# Serial.net
KiCad netlist of a schematic drawn in Altium Designer
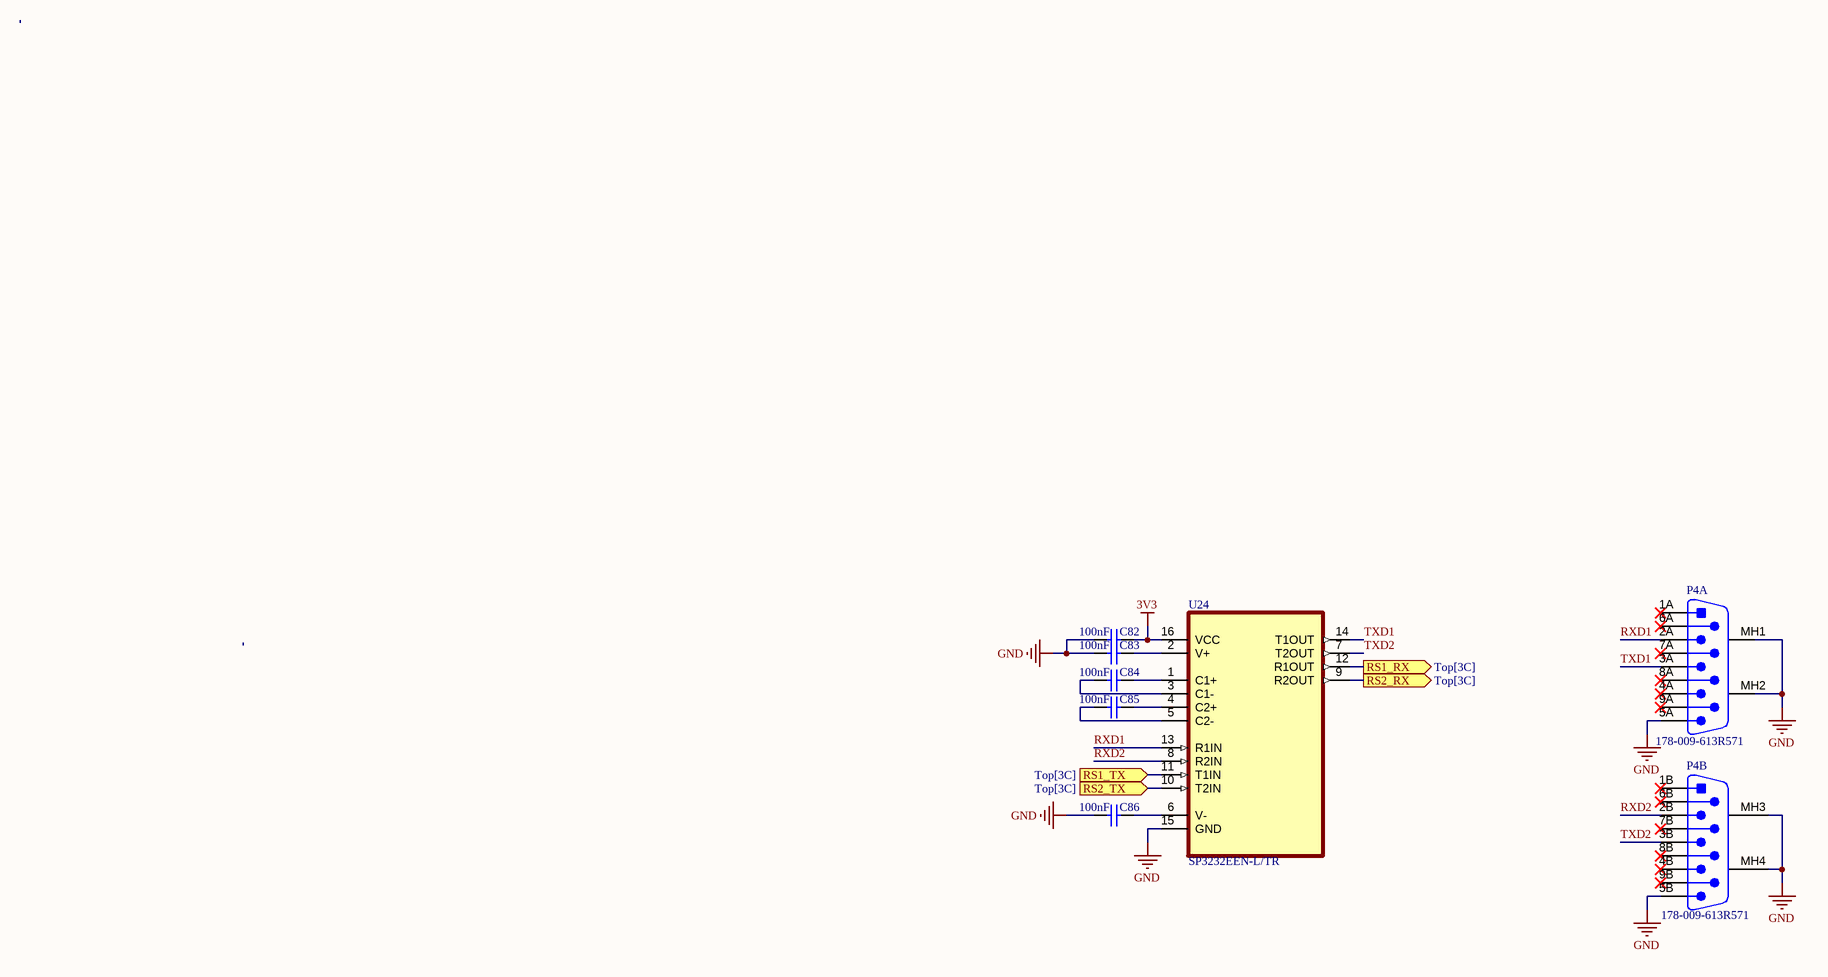
[diagram p0: Serial.SchDoc]

(export (version "E")
  (design (tool "Eeschema 10.0.6"))
  (components
    (comp (ref "C82")
      (value "100nF")
      (description "Capacitor")
      (libsource (lib "Simulation Generic Components") (part "Capacitor"))
    )
    (comp (ref "C83")
      (value "100nF")
      (description "Capacitor")
      (libsource (lib "Simulation Generic Components") (part "Capacitor"))
    )
    (comp (ref "C84")
      (value "100nF")
      (description "Capacitor")
      (libsource (lib "Simulation Generic Components") (part "Capacitor"))
    )
    (comp (ref "C85")
      (value "100nF")
      (description "Capacitor")
      (libsource (lib "Simulation Generic Components") (part "Capacitor"))
    )
    (comp (ref "C86")
      (value "100nF")
      (description "Capacitor")
      (libsource (lib "Simulation Generic Components") (part "Capacitor"))
    )
    (comp (ref "P4")
      (value "178-009-613R571")
      (footprint "NORCO-178-009-613R571_V")
      (description "D-Sub Connector, Stacked Plug, RA, -55 to 105 degC, 18-Pin THD, RoHS, Tray")
      (fields (field (name "MANUFACTURER") "Norcomp"))
      (libsource (lib "Altium Content Vault") (part "CN-2S-4M-D18_A"))
    )
    (comp (ref "U24")
      (value "SP3232EEN-L/TR")
      (footprint "SOIC127P600X175-16N")
      (description "2/2 Transceiver Full RS232 16-SOIC")
      (fields (field (name "MF") "MaxLinear, Inc."))
      (libsource (lib "GSSM Golf Cart") (part "SP3232EEN-L/TR"))
    )
  )
  (nets
    (net (code "1") (name "/RS1_RX") (class "Default")
      (node (ref "U24") (pin "12") (pinfunction "R1OUT_12") (pintype "output"))
    )
    (net (code "2") (name "/RS1_TX") (class "Default")
      (node (ref "U24") (pin "11") (pinfunction "T1IN_11") (pintype "input"))
    )
    (net (code "3") (name "/RS2_RX") (class "Default")
      (node (ref "U24") (pin "9") (pinfunction "R2OUT_9") (pintype "output"))
    )
    (net (code "4") (name "/RS2_TX") (class "Default")
      (node (ref "U24") (pin "10") (pinfunction "T2IN_10") (pintype "input"))
    )
    (net (code "5") (name "/RXD1") (class "Default")
      (node (ref "P4") (pin "2A") (pinfunction "2A_2A") (pintype "passive"))
      (node (ref "U24") (pin "13") (pinfunction "R1IN_13") (pintype "input"))
    )
    (net (code "6") (name "/RXD2") (class "Default")
      (node (ref "P4") (pin "2B") (pinfunction "2B_2B") (pintype "passive"))
      (node (ref "U24") (pin "8") (pinfunction "R2IN_8") (pintype "input"))
    )
    (net (code "7") (name "/TXD1") (class "Default")
      (node (ref "P4") (pin "3A") (pinfunction "6A_3A") (pintype "passive"))
      (node (ref "U24") (pin "14") (pinfunction "T1OUT_14") (pintype "output"))
    )
    (net (code "8") (name "/TXD2") (class "Default")
      (node (ref "P4") (pin "3B") (pinfunction "3B_3B") (pintype "passive"))
      (node (ref "U24") (pin "7") (pinfunction "T2OUT_7") (pintype "output"))
    )
    (net (code "9") (name "3V3") (class "Default")
      (node (ref "C82") (pin "1") (pinfunction "1_1") (pintype "passive"))
      (node (ref "U24") (pin "16") (pinfunction "VCC_16") (pintype "power_in"))
    )
    (net (code "10") (name "GND") (class "Default")
      (node (ref "C82") (pin "2") (pinfunction "2_2") (pintype "passive"))
      (node (ref "C83") (pin "2") (pinfunction "2_2") (pintype "passive"))
      (node (ref "C86") (pin "2") (pinfunction "2_2") (pintype "passive"))
      (node (ref "P4") (pin "5A") (pinfunction "4A_5A") (pintype "passive"))
      (node (ref "P4") (pin "5B") (pinfunction "5B_5B") (pintype "passive"))
      (node (ref "P4") (pin "MH1") (pinfunction "MH1_MH1") (pintype "passive"))
      (node (ref "P4") (pin "MH2") (pinfunction "MH2_MH2") (pintype "passive"))
      (node (ref "P4") (pin "MH3") (pinfunction "MH3_MH3") (pintype "passive"))
      (node (ref "P4") (pin "MH4") (pinfunction "MH4_MH4") (pintype "passive"))
      (node (ref "U24") (pin "15") (pinfunction "GND_15") (pintype "passive"))
    )
    (net (code "11") (name "Net-(U24-C1+)") (class "Default")
      (node (ref "C84") (pin "1") (pinfunction "1_1") (pintype "passive"))
      (node (ref "U24") (pin "1") (pinfunction "C1+_1") (pintype "passive"))
    )
    (net (code "12") (name "Net-(U24-C1-)") (class "Default")
      (node (ref "C84") (pin "2") (pinfunction "2_2") (pintype "passive"))
      (node (ref "U24") (pin "3") (pinfunction "C1-_3") (pintype "passive"))
    )
    (net (code "13") (name "Net-(U24-C2+)") (class "Default")
      (node (ref "C85") (pin "1") (pinfunction "1_1") (pintype "passive"))
      (node (ref "U24") (pin "4") (pinfunction "C2+_4") (pintype "passive"))
    )
    (net (code "14") (name "Net-(U24-C2-)") (class "Default")
      (node (ref "C85") (pin "2") (pinfunction "2_2") (pintype "passive"))
      (node (ref "U24") (pin "5") (pinfunction "C2-_5") (pintype "passive"))
    )
    (net (code "15") (name "Net-(U24-V+)") (class "Default")
      (node (ref "C83") (pin "1") (pinfunction "1_1") (pintype "passive"))
      (node (ref "U24") (pin "2") (pinfunction "V+_2") (pintype "power_in"))
    )
    (net (code "16") (name "Net-(U24-V-)") (class "Default")
      (node (ref "C86") (pin "1") (pinfunction "1_1") (pintype "passive"))
      (node (ref "U24") (pin "6") (pinfunction "V-_6") (pintype "power_in"))
    )
    (net (code "17") (name "unconnected-(P4-Pad1A)") (class "Default")
      (node (ref "P4") (pin "1A") (pinfunction "1A_1A") (pintype "passive+no_connect"))
    )
    (net (code "18") (name "unconnected-(P4-Pad1B)") (class "Default")
      (node (ref "P4") (pin "1B") (pinfunction "1B_1B") (pintype "passive+no_connect"))
    )
    (net (code "19") (name "unconnected-(P4-Pad4B)") (class "Default")
      (node (ref "P4") (pin "4B") (pinfunction "4B_4B") (pintype "passive+no_connect"))
    )
    (net (code "20") (name "unconnected-(P4-Pad6B)") (class "Default")
      (node (ref "P4") (pin "6B") (pinfunction "6B_6B") (pintype "passive+no_connect"))
    )
    (net (code "21") (name "unconnected-(P4-Pad7A)") (class "Default")
      (node (ref "P4") (pin "7A") (pinfunction "7A_7A") (pintype "passive+no_connect"))
    )
    (net (code "22") (name "unconnected-(P4-Pad7B)") (class "Default")
      (node (ref "P4") (pin "7B") (pinfunction "7B_7B") (pintype "passive+no_connect"))
    )
    (net (code "23") (name "unconnected-(P4-Pad8A)") (class "Default")
      (node (ref "P4") (pin "8A") (pinfunction "8A_8A") (pintype "passive+no_connect"))
    )
    (net (code "24") (name "unconnected-(P4-Pad8B)") (class "Default")
      (node (ref "P4") (pin "8B") (pinfunction "8B_8B") (pintype "passive+no_connect"))
    )
    (net (code "25") (name "unconnected-(P4-Pad9A)") (class "Default")
      (node (ref "P4") (pin "9A") (pinfunction "9A_9A") (pintype "passive+no_connect"))
    )
    (net (code "26") (name "unconnected-(P4-Pad9B)") (class "Default")
      (node (ref "P4") (pin "9B") (pinfunction "9B_9B") (pintype "passive+no_connect"))
    )
    (net (code "27") (name "unconnected-(P4A-3A-Pad6A)") (class "Default")
      (node (ref "P4") (pin "6A") (pinfunction "3A_6A") (pintype "passive+no_connect"))
    )
    (net (code "28") (name "unconnected-(P4A-5A-Pad4A)") (class "Default")
      (node (ref "P4") (pin "4A") (pinfunction "5A_4A") (pintype "passive+no_connect"))
    )
  )
)
